# 3_-Connection.net
KiCad netlist of a schematic drawn in Altium Designer
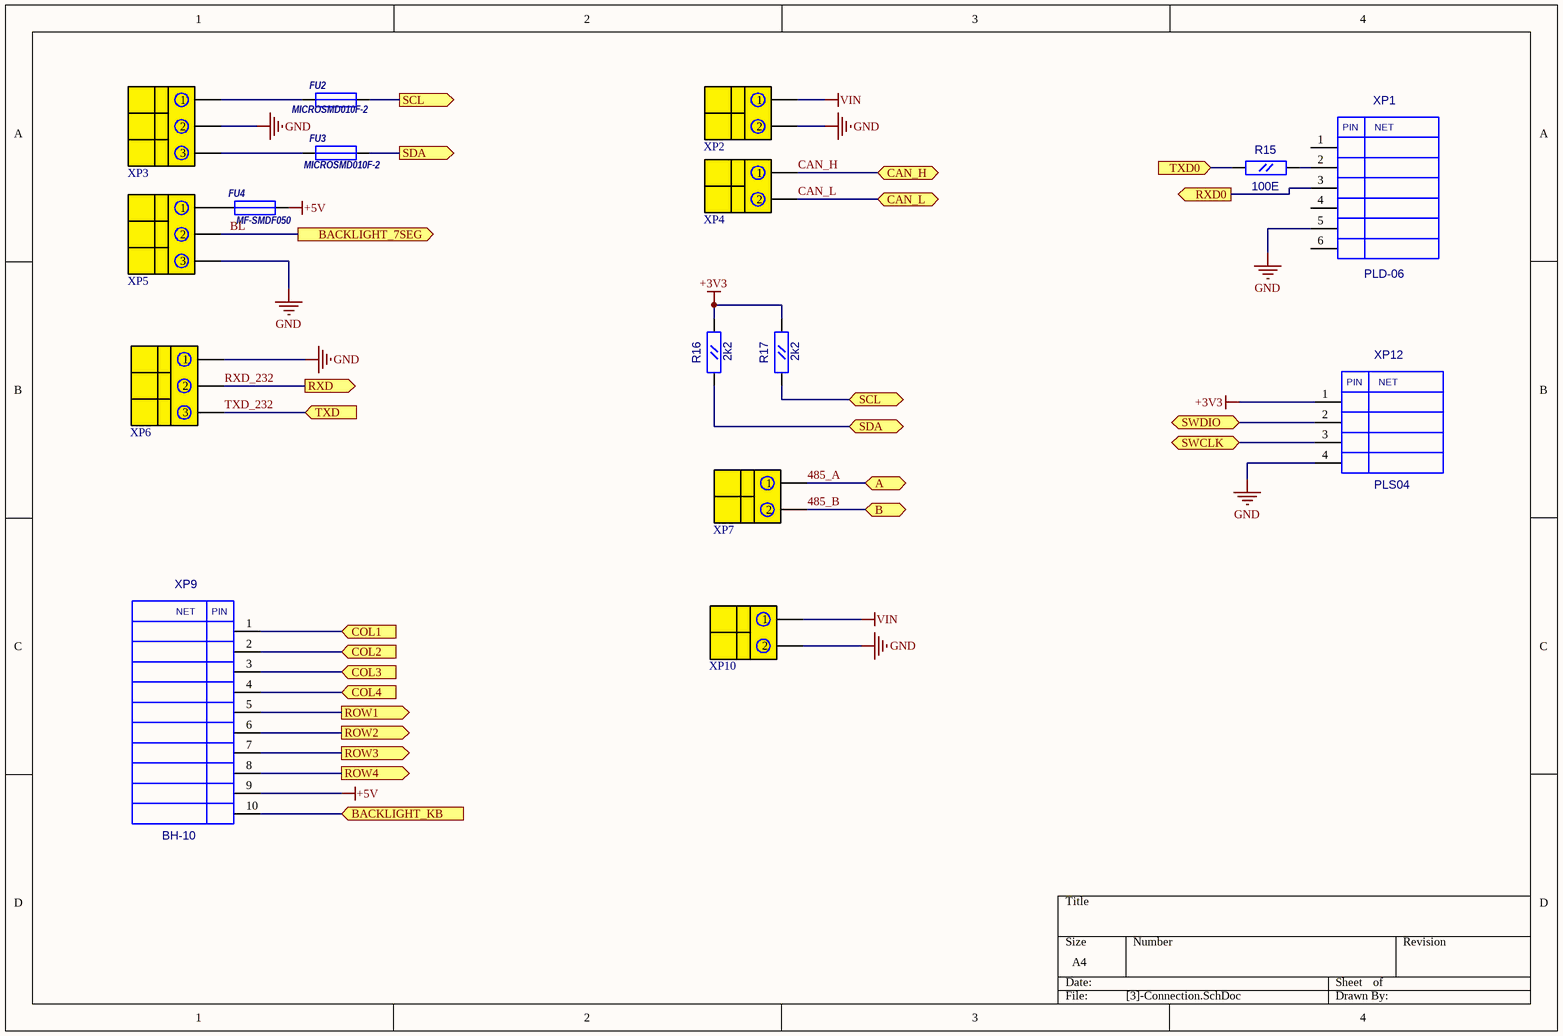
[diagram p0: [3]-Connection.SchDoc]

(export (version "E")
  (design (tool "Eeschema 10.0.6"))
  (components
    (comp (ref "FU2")
      (value "MICROSMD010F-2")
      (footprint "RC1210")
      (description "MICROSMD")
      (libsource (lib "gprs_modem_2") (part "MICROSMD"))
    )
    (comp (ref "FU3")
      (value "MICROSMD010F-2")
      (footprint "RC1210")
      (description "MICROSMD")
      (libsource (lib "gprs_modem_2") (part "MICROSMD"))
    )
    (comp (ref "FU4")
      (value "MF-SMDF050")
      (footprint "MF-SMDF")
      (description "MF-SMDF")
      (libsource (lib "gprs_modem_2") (part "MF-SMDF"))
    )
    (comp (ref "R15")
      (value "100E")
      (footprint "RC0603")
      (description "RC0603")
      (libsource (lib "gprs_modem_2") (part "RC0603"))
    )
    (comp (ref "R16")
      (value "2k2")
      (footprint "RC0603")
      (description "RC0603")
      (libsource (lib "gprs_modem_2") (part "RC0603"))
    )
    (comp (ref "R17")
      (value "2k2")
      (footprint "RC0603")
      (description "RC0603")
      (libsource (lib "gprs_modem_2") (part "RC0603"))
    )
    (comp (ref "XP1")
      (value "PLD-06")
      (footprint "PIN6")
      (description "PLD06")
      (libsource (lib "gprs_modem_2") (part "PLD-06"))
    )
    (comp (ref "XP2")
      (value "DG330-2PIN")
      (footprint "DG330-2PIN")
      (libsource (lib "gprs_modem_2") (part "DG330-2PIN"))
    )
    (comp (ref "XP3")
      (value "DG330-3PIN")
      (footprint "DG330-3PIN")
      (libsource (lib "gprs_modem_2") (part "DG330-3PIN"))
    )
    (comp (ref "XP4")
      (value "DG330-2PIN")
      (footprint "DG330-2PIN")
      (libsource (lib "gprs_modem_2") (part "DG330-2PIN"))
    )
    (comp (ref "XP5")
      (value "DG330-3PIN")
      (footprint "DG330-3PIN")
      (libsource (lib "gprs_modem_2") (part "DG330-3PIN"))
    )
    (comp (ref "XP6")
      (value "DG330-3P")
      (footprint "DG330-3PIN")
      (libsource (lib "gprs_modem_2") (part "DG330-3PIN"))
    )
    (comp (ref "XP7")
      (value "DG330-2PIN")
      (footprint "DG330-2PIN")
      (libsource (lib "gprs_modem_2") (part "DG330-2PIN"))
    )
    (comp (ref "XP9") (value "BH-10") (footprint "BH-10") (libsource (lib "gprs_modem_2") (part "BH-10")))
    (comp (ref "XP10")
      (value "DG330-2PIN")
      (footprint "DG330-2PIN")
      (libsource (lib "gprs_modem_2") (part "DG330-2PIN"))
    )
    (comp (ref "XP12") (value "PLS04") (footprint "PIN04S") (libsource (lib "gprs_modem_2") (part "PLS04")))
  )
  (nets
    (net (code "1") (name "+3V3") (class "Default")
      (node (ref "R16") (pin "2") (pinfunction "B_2") (pintype "passive"))
      (node (ref "R17") (pin "2") (pinfunction "B_2") (pintype "passive"))
      (node (ref "XP12") (pin "1") (pinfunction "1_1") (pintype "passive"))
    )
    (net (code "2") (name "+5V") (class "Default")
      (node (ref "FU4") (pin "2") (pintype "passive"))
      (node (ref "XP9") (pin "9") (pinfunction "9_9") (pintype "passive"))
    )
    (net (code "3") (name "/485_A") (class "Default")
      (node (ref "XP7") (pin "1") (pinfunction "1_1") (pintype "passive"))
    )
    (net (code "4") (name "/485_B") (class "Default")
      (node (ref "XP7") (pin "2") (pinfunction "2_2") (pintype "passive"))
    )
    (net (code "5") (name "/BACKLIGHT_KB") (class "Default")
      (node (ref "XP9") (pin "10") (pinfunction "10_10") (pintype "passive"))
    )
    (net (code "6") (name "/BL") (class "Default")
      (node (ref "XP5") (pin "2") (pinfunction "2_2") (pintype "passive"))
    )
    (net (code "7") (name "/CAN_H") (class "Default")
      (node (ref "XP4") (pin "1") (pinfunction "1_1") (pintype "passive"))
    )
    (net (code "8") (name "/CAN_L") (class "Default")
      (node (ref "XP4") (pin "2") (pinfunction "2_2") (pintype "passive"))
    )
    (net (code "9") (name "/COL1") (class "Default")
      (node (ref "XP9") (pin "1") (pinfunction "1_1") (pintype "passive"))
    )
    (net (code "10") (name "/COL2") (class "Default")
      (node (ref "XP9") (pin "2") (pinfunction "2_2") (pintype "passive"))
    )
    (net (code "11") (name "/COL3") (class "Default")
      (node (ref "XP9") (pin "3") (pinfunction "3_3") (pintype "passive"))
    )
    (net (code "12") (name "/COL4") (class "Default")
      (node (ref "XP9") (pin "4") (pinfunction "4_4") (pintype "passive"))
    )
    (net (code "13") (name "/ROW1") (class "Default")
      (node (ref "XP9") (pin "5") (pinfunction "5_5") (pintype "passive"))
    )
    (net (code "14") (name "/ROW2") (class "Default")
      (node (ref "XP9") (pin "6") (pinfunction "6_6") (pintype "passive"))
    )
    (net (code "15") (name "/ROW3") (class "Default")
      (node (ref "XP9") (pin "7") (pinfunction "7_7") (pintype "passive"))
    )
    (net (code "16") (name "/ROW4") (class "Default")
      (node (ref "XP9") (pin "8") (pinfunction "8_8") (pintype "passive"))
    )
    (net (code "17") (name "/RXD0") (class "Default")
      (node (ref "XP1") (pin "3") (pinfunction "3_3") (pintype "passive"))
    )
    (net (code "18") (name "/RXD_232") (class "Default")
      (node (ref "XP6") (pin "2") (pinfunction "2_2") (pintype "passive"))
    )
    (net (code "19") (name "/SCL") (class "Default")
      (node (ref "FU2") (pin "2") (pintype "passive"))
      (node (ref "R17") (pin "1") (pinfunction "A_1") (pintype "passive"))
    )
    (net (code "20") (name "/SDA") (class "Default")
      (node (ref "FU3") (pin "2") (pintype "passive"))
      (node (ref "R16") (pin "1") (pinfunction "A_1") (pintype "passive"))
    )
    (net (code "21") (name "/SWCLK") (class "Default")
      (node (ref "XP12") (pin "3") (pinfunction "3_3") (pintype "passive"))
    )
    (net (code "22") (name "/SWDIO") (class "Default")
      (node (ref "XP12") (pin "2") (pinfunction "2_2") (pintype "passive"))
    )
    (net (code "23") (name "/TXD0") (class "Default")
      (node (ref "R15") (pin "1") (pinfunction "A_1") (pintype "passive"))
    )
    (net (code "24") (name "/TXD_232") (class "Default")
      (node (ref "XP6") (pin "3") (pinfunction "3_3") (pintype "passive"))
    )
    (net (code "25") (name "GND") (class "Default")
      (node (ref "XP1") (pin "5") (pinfunction "5_5") (pintype "passive"))
      (node (ref "XP10") (pin "2") (pinfunction "2_2") (pintype "passive"))
      (node (ref "XP12") (pin "4") (pinfunction "4_4") (pintype "passive"))
      (node (ref "XP2") (pin "2") (pinfunction "2_2") (pintype "passive"))
      (node (ref "XP3") (pin "2") (pinfunction "2_2") (pintype "passive"))
      (node (ref "XP5") (pin "3") (pinfunction "3_3") (pintype "passive"))
      (node (ref "XP6") (pin "1") (pinfunction "1_1") (pintype "passive"))
    )
    (net (code "26") (name "Net-(FU2-Pad1)") (class "Default")
      (node (ref "FU2") (pin "1") (pintype "passive"))
      (node (ref "XP3") (pin "1") (pinfunction "1_1") (pintype "passive"))
    )
    (net (code "27") (name "Net-(FU3-Pad1)") (class "Default")
      (node (ref "FU3") (pin "1") (pintype "passive"))
      (node (ref "XP3") (pin "3") (pinfunction "3_3") (pintype "passive"))
    )
    (net (code "28") (name "Net-(FU4-Pad1)") (class "Default")
      (node (ref "FU4") (pin "1") (pintype "passive"))
      (node (ref "XP5") (pin "1") (pinfunction "1_1") (pintype "passive"))
    )
    (net (code "29") (name "Net-(R15-B)") (class "Default")
      (node (ref "R15") (pin "2") (pinfunction "B_2") (pintype "passive"))
      (node (ref "XP1") (pin "2") (pinfunction "2_2") (pintype "passive"))
    )
    (net (code "30") (name "VIN") (class "Default")
      (node (ref "XP10") (pin "1") (pinfunction "1_1") (pintype "passive"))
      (node (ref "XP2") (pin "1") (pinfunction "1_1") (pintype "passive"))
    )
    (net (code "31") (name "unconnected-(XP1-Pad1)") (class "Default")
      (node (ref "XP1") (pin "1") (pinfunction "1_1") (pintype "passive"))
    )
    (net (code "32") (name "unconnected-(XP1-Pad4)") (class "Default")
      (node (ref "XP1") (pin "4") (pinfunction "4_4") (pintype "passive"))
    )
    (net (code "33") (name "unconnected-(XP1-Pad6)") (class "Default")
      (node (ref "XP1") (pin "6") (pinfunction "6_6") (pintype "passive"))
    )
  )
)
